# 7_EMAC.net
KiCad netlist of a schematic drawn in Altium Designer
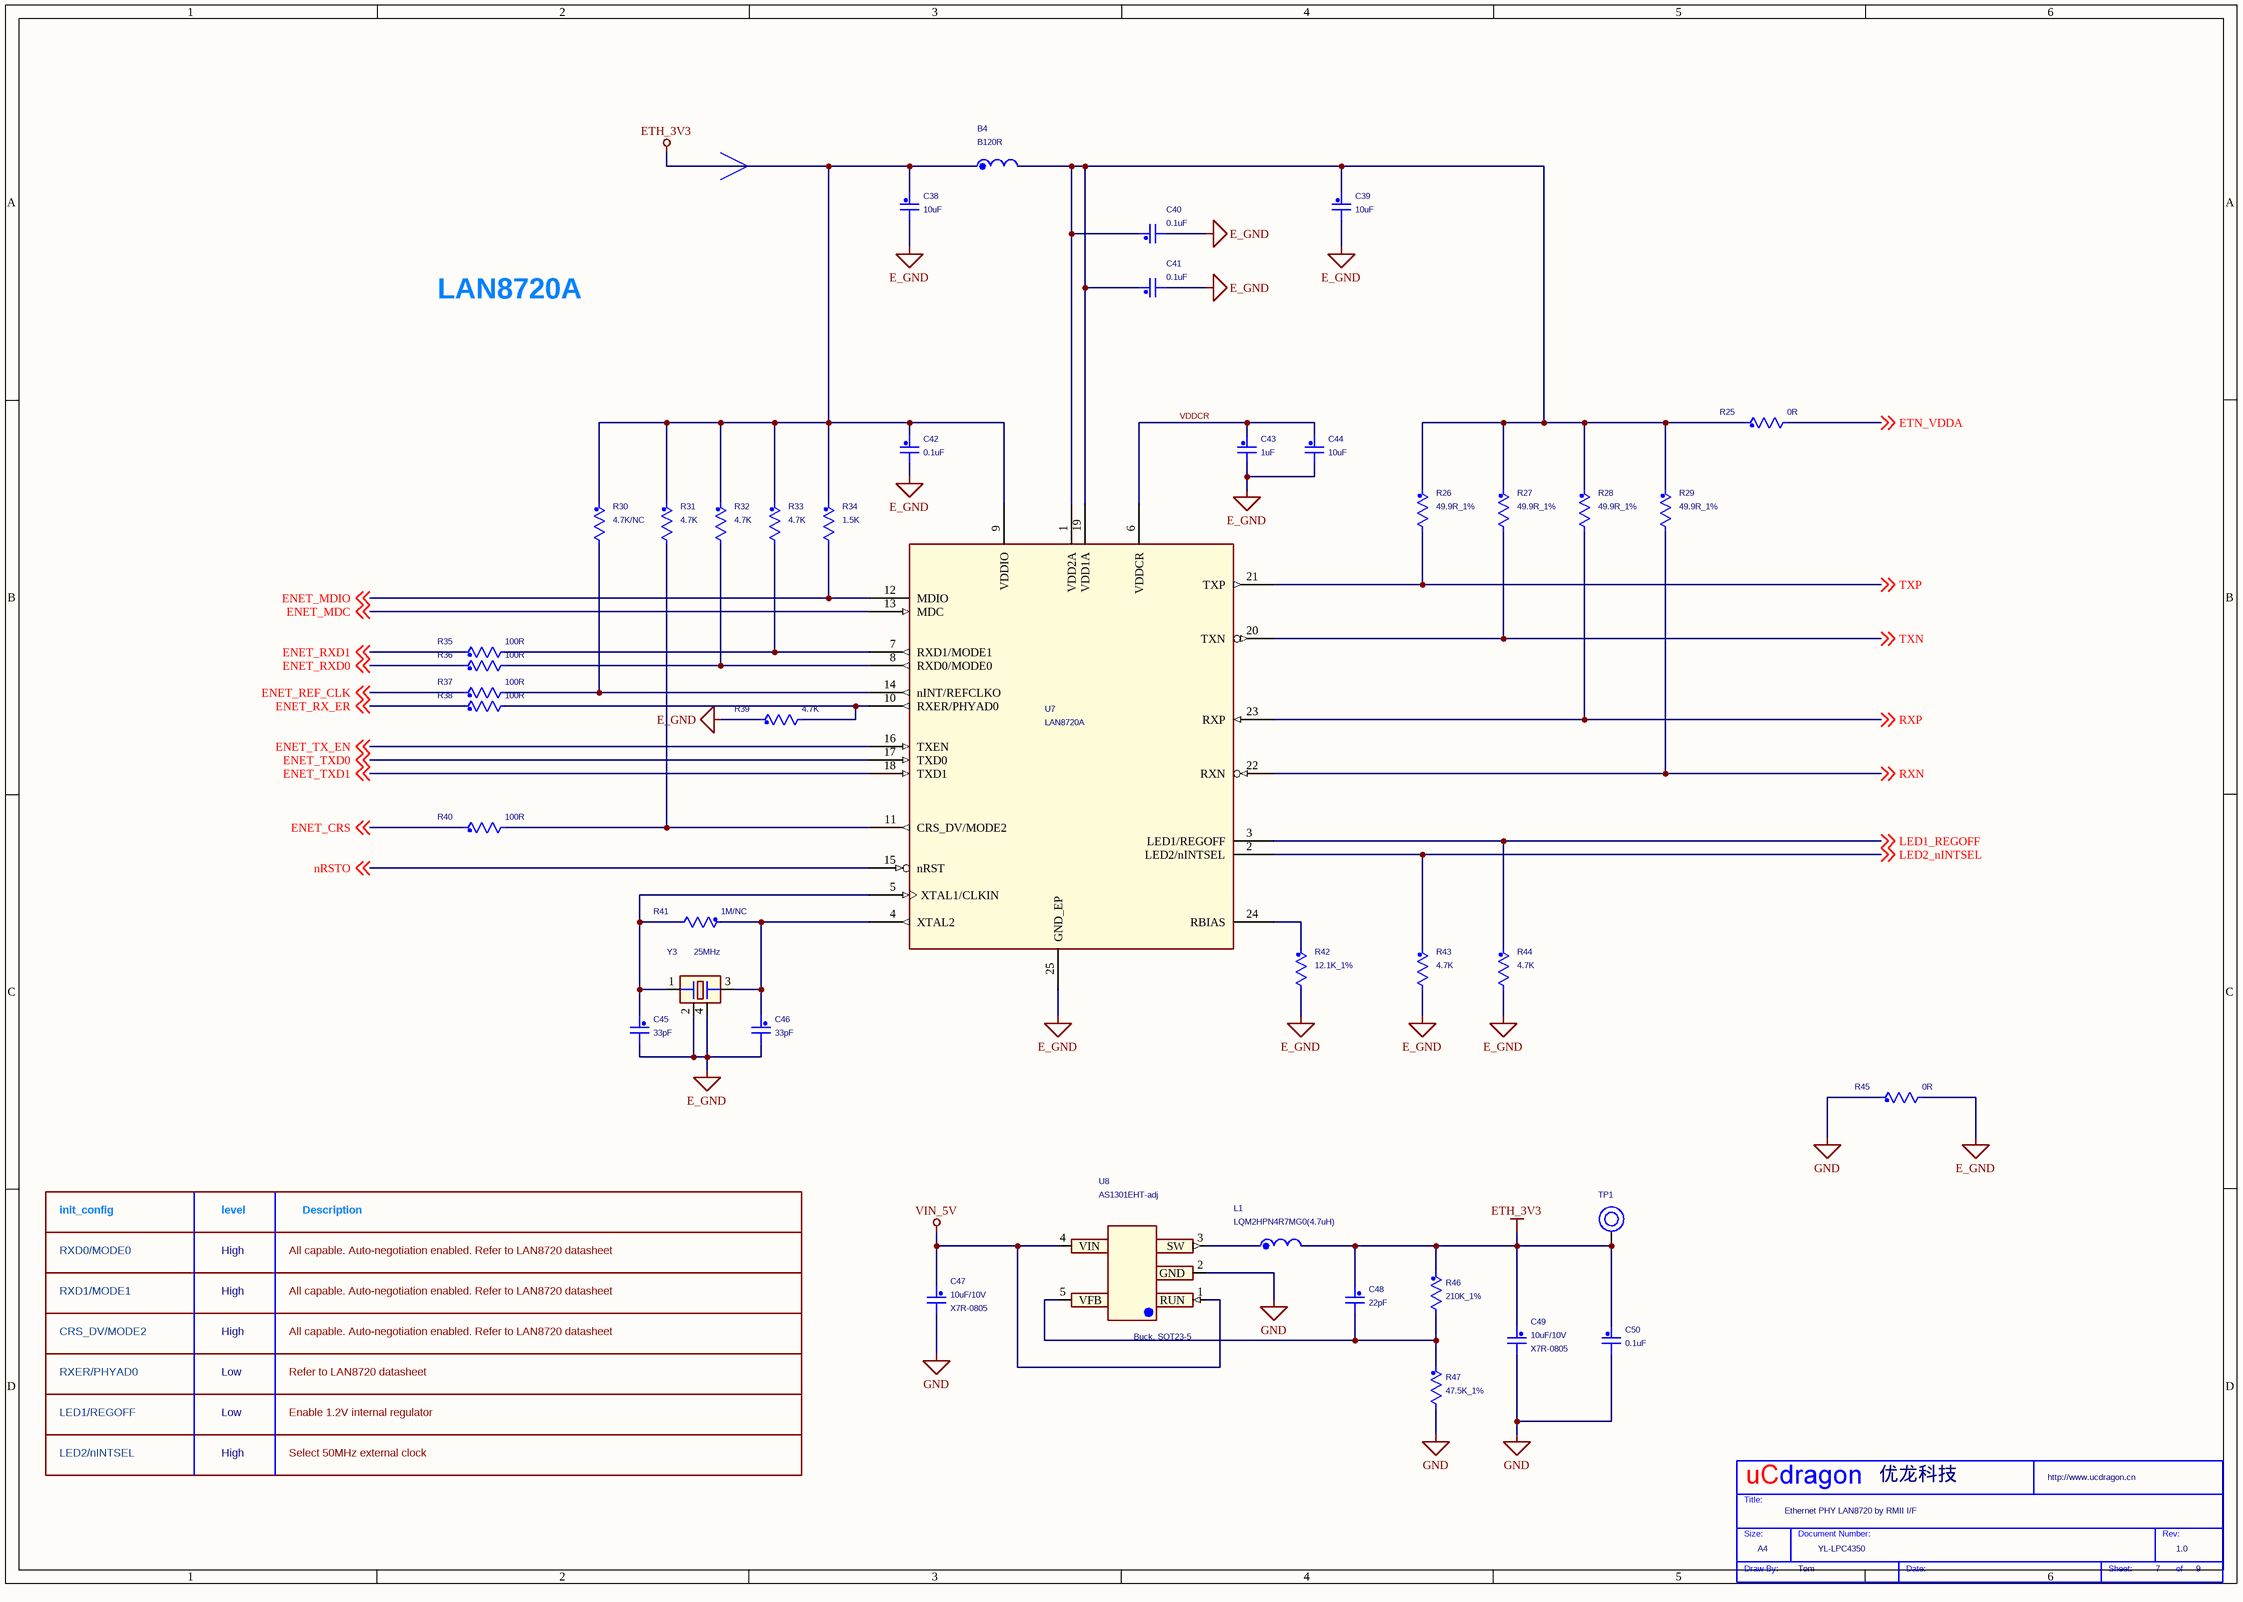
[diagram p0: 7) EMAC.SchDoc]

(export (version "E")
  (design (tool "Eeschema 10.0.6"))
  (components
    (comp (ref "B4") (value "B120R") (libsource (lib "*") (part "Inductor PWR-SMD")))
    (comp (ref "C38")
      (value "10uF")
      (footprint "CAP0805")
      (fields (field (name "VOLTAGE") "16V"))
      (libsource (lib "*") (part "C_Generic"))
    )
    (comp (ref "C39")
      (value "10uF")
      (footprint "CAP0805")
      (fields (field (name "VOLTAGE") "16V"))
      (libsource (lib "*") (part "C_Generic"))
    )
    (comp (ref "C40")
      (value "0.1uF")
      (footprint "CAP0805")
      (fields (field (name "VOLTAGE") "16V"))
      (libsource (lib "*") (part "C_Generic"))
    )
    (comp (ref "C41")
      (value "0.1uF")
      (footprint "CAP0805")
      (fields (field (name "VOLTAGE") "16V"))
      (libsource (lib "*") (part "C_Generic"))
    )
    (comp (ref "C42")
      (value "0.1uF")
      (footprint "CAP0805")
      (fields (field (name "VOLTAGE") "16V"))
      (libsource (lib "*") (part "C_Generic"))
    )
    (comp (ref "C43")
      (value "1uF")
      (footprint "CAP0805")
      (fields (field (name "VOLTAGE") "16V"))
      (libsource (lib "*") (part "C_Generic"))
    )
    (comp (ref "C44")
      (value "10uF")
      (footprint "CAP0805")
      (fields (field (name "VOLTAGE") "16V"))
      (libsource (lib "*") (part "C_Generic"))
    )
    (comp (ref "C45")
      (value "33pF")
      (footprint "CAP0805")
      (fields (field (name "VOLTAGE") "16V"))
      (libsource (lib "*") (part "C_Generic"))
    )
    (comp (ref "C46")
      (value "33pF")
      (footprint "CAP0805")
      (fields (field (name "VOLTAGE") "16V"))
      (libsource (lib "*") (part "C_Generic"))
    )
    (comp (ref "C47")
      (value "10uF/10V")
      (footprint "CAP0805")
      (fields (field (name "VOLTAGE") "16V") (field (name "NOTE") "X7R-0805"))
      (libsource (lib "*") (part "C_Generic"))
    )
    (comp (ref "C48")
      (value "22pF")
      (footprint "CAP0805")
      (fields (field (name "VOLTAGE") "16V"))
      (libsource (lib "*") (part "C_Generic"))
    )
    (comp (ref "C49")
      (value "10uF/10V")
      (footprint "CAP0805")
      (fields (field (name "VOLTAGE") "16V") (field (name "NOTE") "X7R-0805"))
      (libsource (lib "*") (part "C_Generic"))
    )
    (comp (ref "C50")
      (value "0.1uF")
      (footprint "CAP0805")
      (fields (field (name "VOLTAGE") "16V"))
      (libsource (lib "*") (part "C_Generic"))
    )
    (comp (ref "L1") (value "LQM2HPN4R7MG0(4.7uH)") (libsource (lib "*") (part "Inductor PWR-SMD")))
    (comp (ref "R25") (value "0R") (libsource (lib "*") (part "R_Generic_Dup2")))
    (comp (ref "R26") (value "49.9R_1%") (libsource (lib "*") (part "R_Generic_Dup2")))
    (comp (ref "R27") (value "49.9R_1%") (libsource (lib "*") (part "R_Generic_Dup2")))
    (comp (ref "R28") (value "49.9R_1%") (libsource (lib "*") (part "R_Generic_Dup2")))
    (comp (ref "R29") (value "49.9R_1%") (libsource (lib "*") (part "R_Generic_Dup2")))
    (comp (ref "R30") (value "4.7K/NC") (libsource (lib "*") (part "R_Generic_Dup2")))
    (comp (ref "R31") (value "4.7K") (libsource (lib "*") (part "R_Generic_Dup2")))
    (comp (ref "R32") (value "4.7K") (libsource (lib "*") (part "R_Generic_Dup2")))
    (comp (ref "R33") (value "4.7K") (libsource (lib "*") (part "R_Generic_Dup2")))
    (comp (ref "R34") (value "1.5K") (libsource (lib "*") (part "R_Generic_Dup2")))
    (comp (ref "R35") (value "100R") (libsource (lib "*") (part "R_Generic_Dup2")))
    (comp (ref "R36") (value "100R") (libsource (lib "*") (part "R_Generic_Dup2")))
    (comp (ref "R37") (value "100R") (libsource (lib "*") (part "R_Generic_Dup2")))
    (comp (ref "R38") (value "100R") (libsource (lib "*") (part "R_Generic_Dup2")))
    (comp (ref "R39") (value "4.7K") (libsource (lib "*") (part "R_Generic_Dup2")))
    (comp (ref "R40") (value "100R") (libsource (lib "*") (part "R_Generic_Dup2")))
    (comp (ref "R41") (value "1M/NC") (libsource (lib "*") (part "R_Generic_Dup2")))
    (comp (ref "R42") (value "12.1K_1%") (libsource (lib "*") (part "R_Generic_Dup2")))
    (comp (ref "R43") (value "4.7K") (libsource (lib "*") (part "R_Generic_Dup2")))
    (comp (ref "R44") (value "4.7K") (libsource (lib "*") (part "R_Generic_Dup2")))
    (comp (ref "R45") (value "0R") (libsource (lib "*") (part "R_Generic_Dup2")))
    (comp (ref "R46") (value "210K_1%") (libsource (lib "*") (part "R_Generic")))
    (comp (ref "R47") (value "47.5K_1%") (libsource (lib "*") (part "R_Generic")))
    (comp (ref "TP1") (value "3.3V") (footprint "XP-TP-H0.8MM") (libsource (lib "*") (part "TestPoint-HOLE")))
    (comp (ref "U7")
      (value "LAN8720A")
      (footprint "QFN24_4X4MM_EP2P5MM")
      (fields (field (name "PART#") "SMSC LAN8720A-CP"))
      (libsource (lib "*") (part "LAN8720 QFN24"))
    )
    (comp (ref "U8")
      (value "AS1301EHT-adj")
      (fields (field (name "NOTE") "Buck, SOT23-5"))
      (libsource (lib "*") (part "RT8008-PB"))
    )
    (comp (ref "Y3") (value "25MHz") (libsource (lib "*") (part "DSX321G_0")))
  )
  (nets
    (net (code "1") (name "/VDDCR") (class "Default")
      (node (ref "C43") (pin "1") (pinfunction "1_1") (pintype "passive"))
      (node (ref "C44") (pin "1") (pinfunction "1_1") (pintype "passive"))
      (node (ref "U7") (pin "6") (pinfunction "VDDCR_6") (pintype "passive"))
    )
    (net (code "2") (name "ENET_CRS") (class "Default")
      (node (ref "R40") (pin "1") (pinfunction "1_1") (pintype "passive"))
    )
    (net (code "3") (name "ENET_MDC") (class "Default")
      (node (ref "U7") (pin "13") (pinfunction "MDC_13") (pintype "input"))
    )
    (net (code "4") (name "ENET_MDIO") (class "Default")
      (node (ref "R34") (pin "2") (pinfunction "2_2") (pintype "passive"))
      (node (ref "U7") (pin "12") (pinfunction "MDIO_12") (pintype "passive"))
    )
    (net (code "5") (name "ENET_REF_CLK") (class "Default")
      (node (ref "R37") (pin "1") (pinfunction "1_1") (pintype "passive"))
    )
    (net (code "6") (name "ENET_RXD0") (class "Default")
      (node (ref "R36") (pin "1") (pinfunction "1_1") (pintype "passive"))
    )
    (net (code "7") (name "ENET_RXD1") (class "Default")
      (node (ref "R35") (pin "1") (pinfunction "1_1") (pintype "passive"))
    )
    (net (code "8") (name "ENET_RX_ER") (class "Default")
      (node (ref "R38") (pin "1") (pinfunction "1_1") (pintype "passive"))
    )
    (net (code "9") (name "ENET_TXD0") (class "Default")
      (node (ref "U7") (pin "17") (pinfunction "TXD0_17") (pintype "input"))
    )
    (net (code "10") (name "ENET_TXD1") (class "Default")
      (node (ref "U7") (pin "18") (pinfunction "TXD1_18") (pintype "input"))
    )
    (net (code "11") (name "ENET_TX_EN") (class "Default")
      (node (ref "U7") (pin "16") (pinfunction "TXEN_16") (pintype "input"))
    )
    (net (code "12") (name "ETH_3V3") (class "Default")
      (node (ref "B4") (pin "1") (pinfunction "1_1") (pintype "passive"))
      (node (ref "C38") (pin "1") (pinfunction "1_1") (pintype "passive"))
      (node (ref "C42") (pin "1") (pinfunction "1_1") (pintype "passive"))
      (node (ref "C48") (pin "1") (pinfunction "1_1") (pintype "passive"))
      (node (ref "C49") (pin "1") (pinfunction "1_1") (pintype "passive"))
      (node (ref "C50") (pin "1") (pinfunction "1_1") (pintype "passive"))
      (node (ref "L1") (pin "2") (pinfunction "2_2") (pintype "passive"))
      (node (ref "R30") (pin "1") (pinfunction "1_1") (pintype "passive"))
      (node (ref "R31") (pin "1") (pinfunction "1_1") (pintype "passive"))
      (node (ref "R32") (pin "1") (pinfunction "1_1") (pintype "passive"))
      (node (ref "R33") (pin "1") (pinfunction "1_1") (pintype "passive"))
      (node (ref "R34") (pin "1") (pinfunction "1_1") (pintype "passive"))
      (node (ref "R46") (pin "1") (pinfunction "1_1") (pintype "passive"))
      (node (ref "TP1") (pin "1") (pinfunction "1_1") (pintype "passive"))
      (node (ref "U7") (pin "9") (pinfunction "VDDIO_9") (pintype "passive"))
    )
    (net (code "13") (name "ETN_VDDA") (class "Default")
      (node (ref "R25") (pin "2") (pinfunction "2_2") (pintype "passive"))
    )
    (net (code "14") (name "E_GND") (class "Default")
      (node (ref "C38") (pin "2") (pinfunction "2_2") (pintype "passive"))
      (node (ref "C39") (pin "2") (pinfunction "2_2") (pintype "passive"))
      (node (ref "C40") (pin "2") (pinfunction "2_2") (pintype "passive"))
      (node (ref "C41") (pin "2") (pinfunction "2_2") (pintype "passive"))
      (node (ref "C42") (pin "2") (pinfunction "2_2") (pintype "passive"))
      (node (ref "C43") (pin "2") (pinfunction "2_2") (pintype "passive"))
      (node (ref "C44") (pin "2") (pinfunction "2_2") (pintype "passive"))
      (node (ref "C45") (pin "2") (pinfunction "2_2") (pintype "passive"))
      (node (ref "C46") (pin "2") (pinfunction "2_2") (pintype "passive"))
      (node (ref "R39") (pin "1") (pinfunction "1_1") (pintype "passive"))
      (node (ref "R42") (pin "2") (pinfunction "2_2") (pintype "passive"))
      (node (ref "R43") (pin "2") (pinfunction "2_2") (pintype "passive"))
      (node (ref "R44") (pin "2") (pinfunction "2_2") (pintype "passive"))
      (node (ref "R45") (pin "2") (pinfunction "2_2") (pintype "passive"))
      (node (ref "U7") (pin "25") (pinfunction "GND_EP_25") (pintype "passive"))
      (node (ref "Y3") (pin "2") (pinfunction "NC_2") (pintype "passive"))
      (node (ref "Y3") (pin "4") (pinfunction "NC_4") (pintype "passive"))
    )
    (net (code "15") (name "GND") (class "Default")
      (node (ref "C47") (pin "2") (pinfunction "2_2") (pintype "passive"))
      (node (ref "C49") (pin "2") (pinfunction "2_2") (pintype "passive"))
      (node (ref "C50") (pin "2") (pinfunction "2_2") (pintype "passive"))
      (node (ref "R45") (pin "1") (pinfunction "1_1") (pintype "passive"))
      (node (ref "R47") (pin "2") (pinfunction "2_2") (pintype "passive"))
      (node (ref "U8") (pin "2") (pinfunction "GND_2") (pintype "passive"))
    )
    (net (code "16") (name "LED1_REGOFF") (class "Default")
      (node (ref "R44") (pin "1") (pinfunction "1_1") (pintype "passive"))
      (node (ref "U7") (pin "3") (pinfunction "LED1/REGOFF_3") (pintype "passive"))
    )
    (net (code "17") (name "LED2_nINTSEL") (class "Default")
      (node (ref "R43") (pin "1") (pinfunction "1_1") (pintype "passive"))
      (node (ref "U7") (pin "2") (pinfunction "LED2/nINTSEL_2") (pintype "passive"))
    )
    (net (code "18") (name "Net-(U7-CRS_DV{slash}MODE2)") (class "Default")
      (node (ref "R31") (pin "2") (pinfunction "2_2") (pintype "passive"))
      (node (ref "R40") (pin "2") (pinfunction "2_2") (pintype "passive"))
      (node (ref "U7") (pin "11") (pinfunction "CRS_DV/MODE2_11") (pintype "output"))
    )
    (net (code "19") (name "Net-(U7-RBIAS)") (class "Default")
      (node (ref "R42") (pin "1") (pinfunction "1_1") (pintype "passive"))
      (node (ref "U7") (pin "24") (pinfunction "RBIAS_24") (pintype "passive"))
    )
    (net (code "20") (name "Net-(U7-RXD0{slash}MODE0)") (class "Default")
      (node (ref "R32") (pin "2") (pinfunction "2_2") (pintype "passive"))
      (node (ref "R36") (pin "2") (pinfunction "2_2") (pintype "passive"))
      (node (ref "U7") (pin "8") (pinfunction "RXD0/MODE0_8") (pintype "output"))
    )
    (net (code "21") (name "Net-(U7-RXD1{slash}MODE1)") (class "Default")
      (node (ref "R33") (pin "2") (pinfunction "2_2") (pintype "passive"))
      (node (ref "R35") (pin "2") (pinfunction "2_2") (pintype "passive"))
      (node (ref "U7") (pin "7") (pinfunction "RXD1/MODE1_7") (pintype "output"))
    )
    (net (code "22") (name "Net-(U7-RXER{slash}PHYAD0)") (class "Default")
      (node (ref "R38") (pin "2") (pinfunction "2_2") (pintype "passive"))
      (node (ref "R39") (pin "2") (pinfunction "2_2") (pintype "passive"))
      (node (ref "U7") (pin "10") (pinfunction "RXER/PHYAD0_10") (pintype "output"))
    )
    (net (code "23") (name "Net-(U7-VDD1A)") (class "Default")
      (node (ref "B4") (pin "2") (pinfunction "2_2") (pintype "passive"))
      (node (ref "C39") (pin "1") (pinfunction "1_1") (pintype "passive"))
      (node (ref "C40") (pin "1") (pinfunction "1_1") (pintype "passive"))
      (node (ref "C41") (pin "1") (pinfunction "1_1") (pintype "passive"))
      (node (ref "R25") (pin "1") (pinfunction "1_1") (pintype "passive"))
      (node (ref "R26") (pin "1") (pinfunction "1_1") (pintype "passive"))
      (node (ref "R27") (pin "1") (pinfunction "1_1") (pintype "passive"))
      (node (ref "R28") (pin "1") (pinfunction "1_1") (pintype "passive"))
      (node (ref "R29") (pin "1") (pinfunction "1_1") (pintype "passive"))
      (node (ref "U7") (pin "1") (pinfunction "VDD2A_1") (pintype "passive"))
      (node (ref "U7") (pin "19") (pinfunction "VDD1A_19") (pintype "passive"))
    )
    (net (code "24") (name "Net-(U7-XTAL1{slash}CLKIN)") (class "Default")
      (node (ref "C45") (pin "1") (pinfunction "1_1") (pintype "passive"))
      (node (ref "R41") (pin "2") (pinfunction "2_2") (pintype "passive"))
      (node (ref "U7") (pin "5") (pinfunction "XTAL1/CLKIN_5") (pintype "input"))
      (node (ref "Y3") (pin "1") (pinfunction "1_1") (pintype "passive"))
    )
    (net (code "25") (name "Net-(U7-XTAL2)") (class "Default")
      (node (ref "C46") (pin "1") (pinfunction "1_1") (pintype "passive"))
      (node (ref "R41") (pin "1") (pinfunction "1_1") (pintype "passive"))
      (node (ref "U7") (pin "4") (pinfunction "XTAL2_4") (pintype "output"))
      (node (ref "Y3") (pin "3") (pinfunction "3_3") (pintype "passive"))
    )
    (net (code "26") (name "Net-(U7-nINT{slash}REFCLKO)") (class "Default")
      (node (ref "R30") (pin "2") (pinfunction "2_2") (pintype "passive"))
      (node (ref "R37") (pin "2") (pinfunction "2_2") (pintype "passive"))
      (node (ref "U7") (pin "14") (pinfunction "nINT/REFCLKO_14") (pintype "output"))
    )
    (net (code "27") (name "Net-(U8-SW)") (class "Default")
      (node (ref "L1") (pin "1") (pinfunction "1_1") (pintype "passive"))
      (node (ref "U8") (pin "3") (pinfunction "SW_3") (pintype "output"))
    )
    (net (code "28") (name "Net-(U8-VFB)") (class "Default")
      (node (ref "C48") (pin "2") (pinfunction "2_2") (pintype "passive"))
      (node (ref "R46") (pin "2") (pinfunction "2_2") (pintype "passive"))
      (node (ref "R47") (pin "1") (pinfunction "1_1") (pintype "passive"))
      (node (ref "U8") (pin "5") (pinfunction "VFB_5") (pintype "passive"))
    )
    (net (code "29") (name "RXN") (class "Default")
      (node (ref "R29") (pin "2") (pinfunction "2_2") (pintype "passive"))
      (node (ref "U7") (pin "22") (pinfunction "RXN_22") (pintype "input"))
    )
    (net (code "30") (name "RXP") (class "Default")
      (node (ref "R28") (pin "2") (pinfunction "2_2") (pintype "passive"))
      (node (ref "U7") (pin "23") (pinfunction "RXP_23") (pintype "input"))
    )
    (net (code "31") (name "TXN") (class "Default")
      (node (ref "R27") (pin "2") (pinfunction "2_2") (pintype "passive"))
      (node (ref "U7") (pin "20") (pinfunction "TXN_20") (pintype "output"))
    )
    (net (code "32") (name "TXP") (class "Default")
      (node (ref "R26") (pin "2") (pinfunction "2_2") (pintype "passive"))
      (node (ref "U7") (pin "21") (pinfunction "TXP_21") (pintype "output"))
    )
    (net (code "33") (name "VIN_5V") (class "Default")
      (node (ref "C47") (pin "1") (pinfunction "1_1") (pintype "passive"))
      (node (ref "U8") (pin "1") (pinfunction "RUN_1") (pintype "input"))
      (node (ref "U8") (pin "4") (pinfunction "VIN_4") (pintype "passive"))
    )
    (net (code "34") (name "nRSTO") (class "Default")
      (node (ref "U7") (pin "15") (pinfunction "nRST_15") (pintype "input"))
    )
  )
)
